# design.net
KiCad netlist of a schematic drawn in Altium Designer
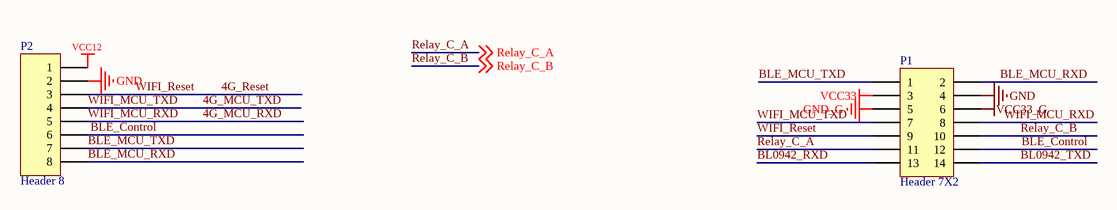
[diagram p0: 连接.SchDoc]

(export (version "E")
  (design (tool "Eeschema 10.0.6"))
  (components
    (comp (ref "P1")
      (value "Header 7X2")
      (footprint "HDR2X7")
      (description "Header, 7-Pin, Dual row")
      (fields (field (name "PUBLISHER") "Altium Limited"))
      (libsource (lib "Miscellaneous Connectors") (part "Header 7X2"))
    )
    (comp (ref "P2")
      (value "Header 8")
      (footprint "HDR1X8")
      (description "Header, 8-Pin")
      (fields (field (name "PUBLISHER") "Altium Limited"))
      (libsource (lib "Miscellaneous Connectors") (part "Header 8"))
    )
  )
  (nets
    (net (code "1") (name "/4G_MCU_RXD") (class "Default")
      (node (ref "P1") (pin "8") (pinfunction "8_8") (pintype "passive"))
      (node (ref "P2") (pin "5") (pinfunction "5_5") (pintype "passive"))
    )
    (net (code "2") (name "/4G_MCU_TXD") (class "Default")
      (node (ref "P1") (pin "7") (pinfunction "7_7") (pintype "passive"))
      (node (ref "P2") (pin "4") (pinfunction "4_4") (pintype "passive"))
    )
    (net (code "3") (name "/4G_Reset") (class "Default")
      (node (ref "P1") (pin "9") (pinfunction "9_9") (pintype "passive"))
      (node (ref "P2") (pin "3") (pinfunction "3_3") (pintype "passive"))
    )
    (net (code "4") (name "/BL0942_RXD") (class "Default")
      (node (ref "P1") (pin "13") (pinfunction "13_13") (pintype "passive"))
    )
    (net (code "5") (name "/BL0942_TXD") (class "Default")
      (node (ref "P1") (pin "14") (pinfunction "14_14") (pintype "passive"))
    )
    (net (code "6") (name "/BLE_Control") (class "Default")
      (node (ref "P1") (pin "12") (pinfunction "12_12") (pintype "passive"))
      (node (ref "P2") (pin "6") (pinfunction "6_6") (pintype "passive"))
    )
    (net (code "7") (name "/BLE_MCU_RXD") (class "Default")
      (node (ref "P1") (pin "2") (pinfunction "2_2") (pintype "passive"))
      (node (ref "P2") (pin "8") (pinfunction "8_8") (pintype "passive"))
    )
    (net (code "8") (name "/BLE_MCU_TXD") (class "Default")
      (node (ref "P1") (pin "1") (pinfunction "1_1") (pintype "passive"))
      (node (ref "P2") (pin "7") (pinfunction "7_7") (pintype "passive"))
    )
    (net (code "9") (name "GND") (class "Default")
      (node (ref "P1") (pin "4") (pinfunction "4_4") (pintype "passive"))
      (node (ref "P2") (pin "2") (pinfunction "2_2") (pintype "passive"))
    )
    (net (code "10") (name "GND_G") (class "Default")
      (node (ref "P1") (pin "5") (pinfunction "5_5") (pintype "passive"))
    )
    (net (code "11") (name "Relay_C_A") (class "Default")
      (node (ref "P1") (pin "11") (pinfunction "11_11") (pintype "passive"))
    )
    (net (code "12") (name "Relay_C_B") (class "Default")
      (node (ref "P1") (pin "10") (pinfunction "10_10") (pintype "passive"))
    )
    (net (code "13") (name "VCC12") (class "Default")
      (node (ref "P2") (pin "1") (pinfunction "1_1") (pintype "passive"))
    )
    (net (code "14") (name "VCC33") (class "Default")
      (node (ref "P1") (pin "3") (pinfunction "3_3") (pintype "passive"))
    )
    (net (code "15") (name "VCC33_G") (class "Default")
      (node (ref "P1") (pin "6") (pinfunction "6_6") (pintype "passive"))
    )
  )
)
